# DaisyChainController.net
KiCad netlist of a schematic drawn in EAGLE
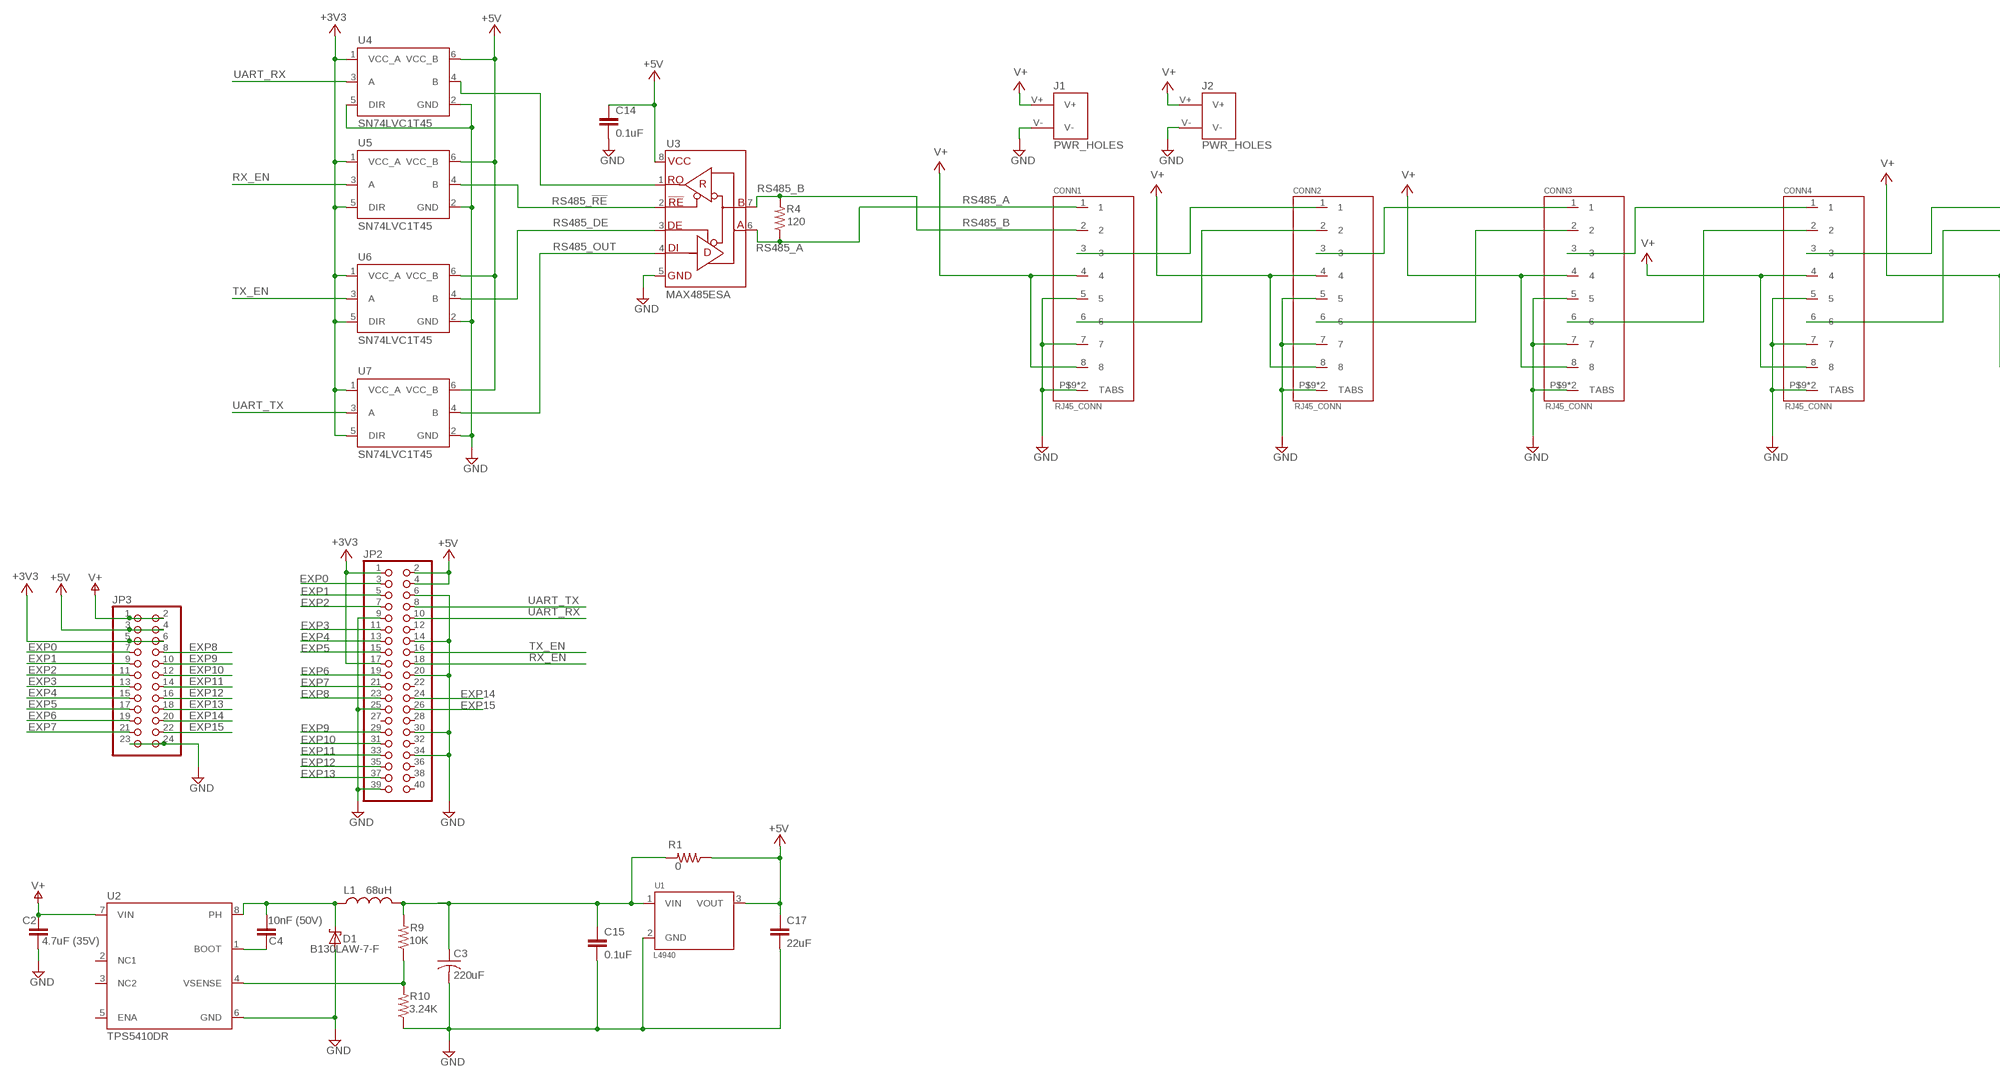
[diagram p0: schematic, sheet 1, part 1 of 2]
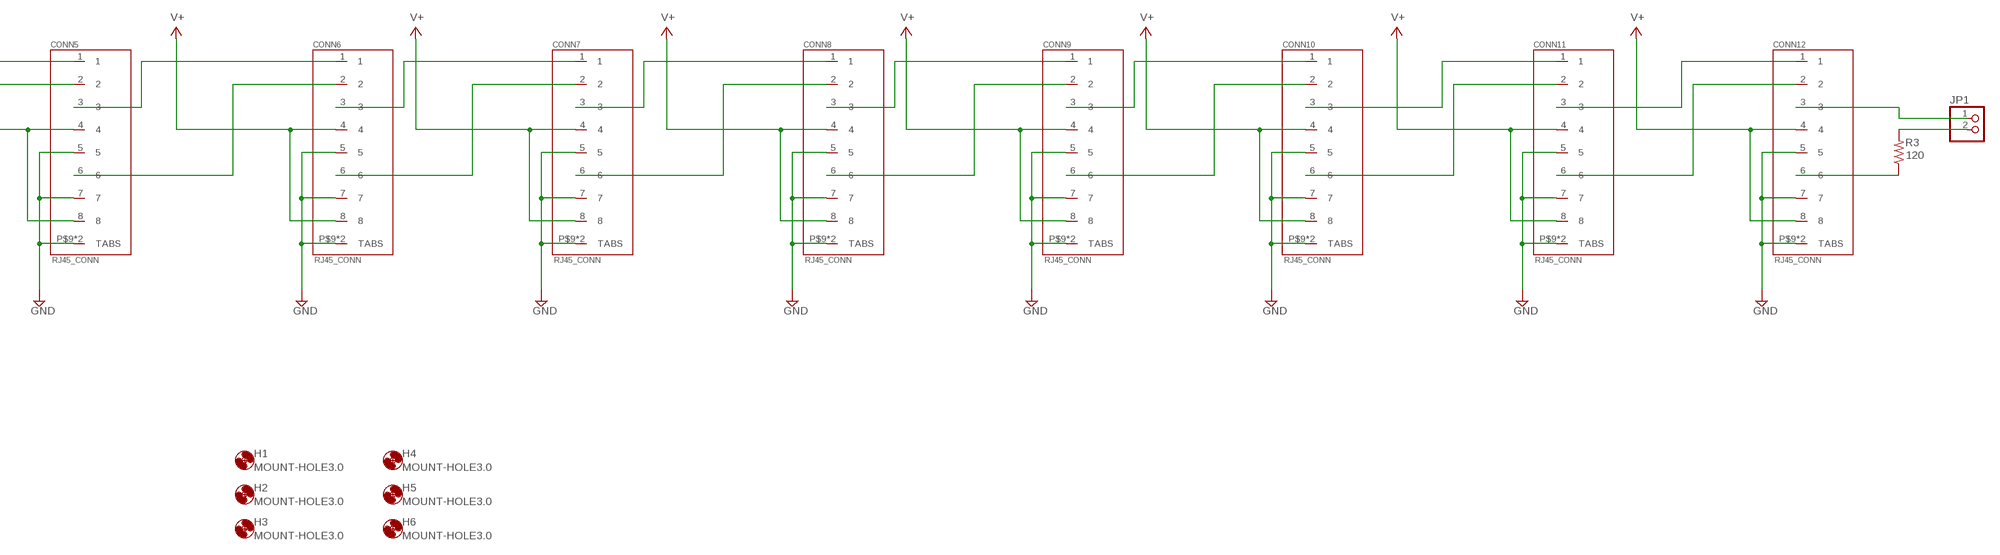
[diagram p1: schematic, sheet 1, part 2 of 2]

(export (version "E")
  (design (tool "Eeschema 10.0.6"))
  (components
    (comp (ref "C2")
      (value "4.7uF (35V)")
      (footprint "eagle-import:C0805")
      (libsource (lib "eagle-import") (part "C-EUC0805"))
    )
    (comp (ref "C3")
      (value "220uF")
      (footprint "eagle-import:KEMET_D_CAP")
      (libsource (lib "eagle-import") (part "TANT_CAP_D"))
    )
    (comp (ref "C4")
      (value "10nF (50V)")
      (footprint "eagle-import:C0805")
      (libsource (lib "eagle-import") (part "C-EUC0805"))
    )
    (comp (ref "C14")
      (value "0.1uF")
      (footprint "eagle-import:C0805")
      (libsource (lib "eagle-import") (part "C-EUC0805"))
    )
    (comp (ref "C15")
      (value "0.1uF")
      (footprint "eagle-import:C0805")
      (libsource (lib "eagle-import") (part "C-EUC0805"))
    )
    (comp (ref "C17")
      (value "22uF")
      (footprint "eagle-import:C0805")
      (libsource (lib "eagle-import") (part "C-EUC0805"))
    )
    (comp (ref "CONN1")
      (value "RJ45_CONN")
      (footprint "eagle-import:RJ45_VERT")
      (libsource (lib "eagle-import") (part "RJ45_CONN"))
    )
    (comp (ref "CONN2")
      (value "RJ45_CONN")
      (footprint "eagle-import:RJ45_VERT")
      (libsource (lib "eagle-import") (part "RJ45_CONN"))
    )
    (comp (ref "CONN3")
      (value "RJ45_CONN")
      (footprint "eagle-import:RJ45_VERT")
      (libsource (lib "eagle-import") (part "RJ45_CONN"))
    )
    (comp (ref "CONN4")
      (value "RJ45_CONN")
      (footprint "eagle-import:RJ45_VERT")
      (libsource (lib "eagle-import") (part "RJ45_CONN"))
    )
    (comp (ref "CONN5")
      (value "RJ45_CONN")
      (footprint "eagle-import:RJ45_VERT")
      (libsource (lib "eagle-import") (part "RJ45_CONN"))
    )
    (comp (ref "CONN6")
      (value "RJ45_CONN")
      (footprint "eagle-import:RJ45_VERT")
      (libsource (lib "eagle-import") (part "RJ45_CONN"))
    )
    (comp (ref "CONN7")
      (value "RJ45_CONN")
      (footprint "eagle-import:RJ45_VERT")
      (libsource (lib "eagle-import") (part "RJ45_CONN"))
    )
    (comp (ref "CONN8")
      (value "RJ45_CONN")
      (footprint "eagle-import:RJ45_VERT")
      (libsource (lib "eagle-import") (part "RJ45_CONN"))
    )
    (comp (ref "CONN9")
      (value "RJ45_CONN")
      (footprint "eagle-import:RJ45_VERT")
      (libsource (lib "eagle-import") (part "RJ45_CONN"))
    )
    (comp (ref "CONN10")
      (value "RJ45_CONN")
      (footprint "eagle-import:RJ45_VERT")
      (libsource (lib "eagle-import") (part "RJ45_CONN"))
    )
    (comp (ref "CONN11")
      (value "RJ45_CONN")
      (footprint "eagle-import:RJ45_VERT")
      (libsource (lib "eagle-import") (part "RJ45_CONN"))
    )
    (comp (ref "CONN12")
      (value "RJ45_CONN")
      (footprint "eagle-import:RJ45_VERT")
      (libsource (lib "eagle-import") (part "RJ45_CONN"))
    )
    (comp (ref "D1")
      (value "B130LAW-7-F")
      (footprint "eagle-import:SOD123")
      (libsource (lib "eagle-import") (part "B130LAW-7-F"))
    )
    (comp (ref "H1")
      (value "MOUNT-HOLE3.0")
      (footprint "eagle-import:3,0")
      (libsource (lib "eagle-import") (part "MOUNT-HOLE3.0"))
    )
    (comp (ref "H2")
      (value "MOUNT-HOLE3.0")
      (footprint "eagle-import:3,0")
      (libsource (lib "eagle-import") (part "MOUNT-HOLE3.0"))
    )
    (comp (ref "H3")
      (value "MOUNT-HOLE3.0")
      (footprint "eagle-import:3,0")
      (libsource (lib "eagle-import") (part "MOUNT-HOLE3.0"))
    )
    (comp (ref "H4")
      (value "MOUNT-HOLE3.0")
      (footprint "eagle-import:3,0")
      (libsource (lib "eagle-import") (part "MOUNT-HOLE3.0"))
    )
    (comp (ref "H5")
      (value "MOUNT-HOLE3.0")
      (footprint "eagle-import:3,0")
      (libsource (lib "eagle-import") (part "MOUNT-HOLE3.0"))
    )
    (comp (ref "H6")
      (value "MOUNT-HOLE3.0")
      (footprint "eagle-import:3,0")
      (libsource (lib "eagle-import") (part "MOUNT-HOLE3.0"))
    )
    (comp (ref "J1")
      (value "PWR_HOLES")
      (footprint "eagle-import:PWR_HOLES")
      (libsource (lib "eagle-import") (part "PWR_HOLES"))
    )
    (comp (ref "J2")
      (value "PWR_HOLES")
      (footprint "eagle-import:PWR_HOLES")
      (libsource (lib "eagle-import") (part "PWR_HOLES"))
    )
    (comp (ref "JP1")
      (value "PINHD-1X2")
      (footprint "eagle-import:1X02")
      (libsource (lib "eagle-import") (part "PINHD-1X2"))
    )
    (comp (ref "JP2")
      (value "PINHD-2X20/90")
      (footprint "eagle-import:2X20_90")
      (libsource (lib "eagle-import") (part "PINHD-2X20/90"))
    )
    (comp (ref "JP3")
      (value "PINHD-2X12")
      (footprint "eagle-import:2X12")
      (libsource (lib "eagle-import") (part "PINHD-2X12"))
    )
    (comp (ref "L1")
      (value "68uH")
      (footprint "eagle-import:CDRH127R")
      (libsource (lib "eagle-import") (part "L_CDRH127"))
    )
    (comp (ref "R1")
      (value "0")
      (footprint "eagle-import:R0805")
      (libsource (lib "eagle-import") (part "R-US_R0805"))
    )
    (comp (ref "R3")
      (value "120")
      (footprint "eagle-import:R0805")
      (libsource (lib "eagle-import") (part "R-US_R0805"))
    )
    (comp (ref "R4")
      (value "120")
      (footprint "eagle-import:R0805")
      (libsource (lib "eagle-import") (part "R-US_R0805"))
    )
    (comp (ref "R9")
      (value "10K")
      (footprint "eagle-import:R0805")
      (libsource (lib "eagle-import") (part "R-US_R0805"))
    )
    (comp (ref "R10")
      (value "3.24K")
      (footprint "eagle-import:R0805")
      (libsource (lib "eagle-import") (part "R-US_R0805"))
    )
    (comp (ref "U1")
      (value "L4940")
      (footprint "eagle-import:TO220")
      (libsource (lib "eagle-import") (part "L4940"))
    )
    (comp (ref "U2")
      (value "TPS5410DR")
      (footprint "eagle-import:SO08")
      (libsource (lib "eagle-import") (part "TPS5410DR"))
    )
    (comp (ref "U3")
      (value "MAX485ESA")
      (footprint "eagle-import:SO08")
      (libsource (lib "eagle-import") (part "MAX485ESA"))
    )
    (comp (ref "U4")
      (value "SN74LVC1T45")
      (footprint "eagle-import:SOT23-6")
      (libsource (lib "eagle-import") (part "SN74LVC1T45"))
    )
    (comp (ref "U5")
      (value "SN74LVC1T45")
      (footprint "eagle-import:SOT23-6")
      (libsource (lib "eagle-import") (part "SN74LVC1T45"))
    )
    (comp (ref "U6")
      (value "SN74LVC1T45")
      (footprint "eagle-import:SOT23-6")
      (libsource (lib "eagle-import") (part "SN74LVC1T45"))
    )
    (comp (ref "U7")
      (value "SN74LVC1T45")
      (footprint "eagle-import:SOT23-6")
      (libsource (lib "eagle-import") (part "SN74LVC1T45"))
    )
  )
  (nets
    (net (code "1") (name "+3V3") (class "Default")
      (node (ref "JP2") (pin "1") (pinfunction "1_1") (pintype "passive"))
      (node (ref "JP2") (pin "17") (pinfunction "17_17") (pintype "passive"))
      (node (ref "JP3") (pin "5") (pinfunction "5_5") (pintype "passive"))
      (node (ref "JP3") (pin "6") (pinfunction "6_6") (pintype "passive"))
      (node (ref "U4") (pin "1") (pinfunction "VCC_A_1") (pintype "power_in"))
      (node (ref "U5") (pin "1") (pinfunction "VCC_A_1") (pintype "power_in"))
      (node (ref "U5") (pin "5") (pinfunction "DIR_5") (pintype "input"))
      (node (ref "U6") (pin "1") (pinfunction "VCC_A_1") (pintype "power_in"))
      (node (ref "U6") (pin "5") (pinfunction "DIR_5") (pintype "input"))
      (node (ref "U7") (pin "1") (pinfunction "VCC_A_1") (pintype "power_in"))
      (node (ref "U7") (pin "5") (pinfunction "DIR_5") (pintype "input"))
    )
    (net (code "2") (name "+5V") (class "Default")
      (node (ref "C14") (pin "1") (pinfunction "1_1") (pintype "passive"))
      (node (ref "C17") (pin "1") (pinfunction "1_1") (pintype "passive"))
      (node (ref "JP2") (pin "2") (pinfunction "2_2") (pintype "passive"))
      (node (ref "JP2") (pin "4") (pinfunction "4_4") (pintype "passive"))
      (node (ref "JP3") (pin "3") (pinfunction "3_3") (pintype "passive"))
      (node (ref "JP3") (pin "4") (pinfunction "4_4") (pintype "passive"))
      (node (ref "R1") (pin "1") (pinfunction "1_1") (pintype "passive"))
      (node (ref "U1") (pin "3") (pinfunction "VOUT_3") (pintype "power_in"))
      (node (ref "U3") (pin "8") (pinfunction "VCC_8") (pintype "power_in"))
      (node (ref "U4") (pin "6") (pinfunction "VCC_B_6") (pintype "power_in"))
      (node (ref "U5") (pin "6") (pinfunction "VCC_B_6") (pintype "power_in"))
      (node (ref "U6") (pin "6") (pinfunction "VCC_B_6") (pintype "power_in"))
      (node (ref "U7") (pin "6") (pinfunction "VCC_B_6") (pintype "power_in"))
    )
    (net (code "3") (name "/EXP0") (class "Default")
      (node (ref "JP2") (pin "3") (pinfunction "3_3") (pintype "passive"))
      (node (ref "JP3") (pin "7") (pinfunction "7_7") (pintype "passive"))
    )
    (net (code "4") (name "/EXP1") (class "Default")
      (node (ref "JP2") (pin "5") (pinfunction "5_5") (pintype "passive"))
      (node (ref "JP3") (pin "9") (pinfunction "9_9") (pintype "passive"))
    )
    (net (code "5") (name "/EXP2") (class "Default")
      (node (ref "JP2") (pin "7") (pinfunction "7_7") (pintype "passive"))
      (node (ref "JP3") (pin "11") (pinfunction "11_11") (pintype "passive"))
    )
    (net (code "6") (name "/EXP3") (class "Default")
      (node (ref "JP2") (pin "11") (pinfunction "11_11") (pintype "passive"))
      (node (ref "JP3") (pin "13") (pinfunction "13_13") (pintype "passive"))
    )
    (net (code "7") (name "/EXP4") (class "Default")
      (node (ref "JP2") (pin "13") (pinfunction "13_13") (pintype "passive"))
      (node (ref "JP3") (pin "15") (pinfunction "15_15") (pintype "passive"))
    )
    (net (code "8") (name "/EXP5") (class "Default")
      (node (ref "JP2") (pin "15") (pinfunction "15_15") (pintype "passive"))
      (node (ref "JP3") (pin "17") (pinfunction "17_17") (pintype "passive"))
    )
    (net (code "9") (name "/EXP6") (class "Default")
      (node (ref "JP2") (pin "19") (pinfunction "19_19") (pintype "passive"))
      (node (ref "JP3") (pin "19") (pinfunction "19_19") (pintype "passive"))
    )
    (net (code "10") (name "/EXP7") (class "Default")
      (node (ref "JP2") (pin "21") (pinfunction "21_21") (pintype "passive"))
      (node (ref "JP3") (pin "21") (pinfunction "21_21") (pintype "passive"))
    )
    (net (code "11") (name "/EXP8") (class "Default")
      (node (ref "JP2") (pin "23") (pinfunction "23_23") (pintype "passive"))
      (node (ref "JP3") (pin "8") (pinfunction "8_8") (pintype "passive"))
    )
    (net (code "12") (name "/EXP9") (class "Default")
      (node (ref "JP2") (pin "29") (pinfunction "29_29") (pintype "passive"))
      (node (ref "JP3") (pin "10") (pinfunction "10_10") (pintype "passive"))
    )
    (net (code "13") (name "/EXP10") (class "Default")
      (node (ref "JP2") (pin "31") (pinfunction "31_31") (pintype "passive"))
      (node (ref "JP3") (pin "12") (pinfunction "12_12") (pintype "passive"))
    )
    (net (code "14") (name "/EXP11") (class "Default")
      (node (ref "JP2") (pin "33") (pinfunction "33_33") (pintype "passive"))
      (node (ref "JP3") (pin "14") (pinfunction "14_14") (pintype "passive"))
    )
    (net (code "15") (name "/EXP12") (class "Default")
      (node (ref "JP2") (pin "35") (pinfunction "35_35") (pintype "passive"))
      (node (ref "JP3") (pin "16") (pinfunction "16_16") (pintype "passive"))
    )
    (net (code "16") (name "/EXP13") (class "Default")
      (node (ref "JP2") (pin "37") (pinfunction "37_37") (pintype "passive"))
      (node (ref "JP3") (pin "18") (pinfunction "18_18") (pintype "passive"))
    )
    (net (code "17") (name "/EXP14") (class "Default")
      (node (ref "JP2") (pin "24") (pinfunction "24_24") (pintype "passive"))
      (node (ref "JP3") (pin "20") (pinfunction "20_20") (pintype "passive"))
    )
    (net (code "18") (name "/EXP15") (class "Default")
      (node (ref "JP2") (pin "26") (pinfunction "26_26") (pintype "passive"))
      (node (ref "JP3") (pin "22") (pinfunction "22_22") (pintype "passive"))
    )
    (net (code "19") (name "/RS485_A") (class "Default")
      (node (ref "CONN1") (pin "1") (pinfunction "1_1") (pintype "bidirectional"))
      (node (ref "R4") (pin "1") (pinfunction "1_1") (pintype "passive"))
      (node (ref "U3") (pin "6") (pinfunction "A_6") (pintype "bidirectional"))
    )
    (net (code "20") (name "/RS485_B") (class "Default")
      (node (ref "CONN1") (pin "2") (pinfunction "2_2") (pintype "bidirectional"))
      (node (ref "R4") (pin "2") (pinfunction "2_2") (pintype "passive"))
      (node (ref "U3") (pin "7") (pinfunction "B_7") (pintype "bidirectional"))
    )
    (net (code "21") (name "/RS485_DE") (class "Default")
      (node (ref "U3") (pin "3") (pinfunction "DE_3") (pintype "input"))
      (node (ref "U6") (pin "4") (pinfunction "B_4") (pintype "bidirectional"))
    )
    (net (code "22") (name "/RS485_OUT") (class "Default")
      (node (ref "U3") (pin "4") (pinfunction "DI_4") (pintype "input"))
      (node (ref "U7") (pin "4") (pinfunction "B_4") (pintype "bidirectional"))
    )
    (net (code "23") (name "/RS485_~{RE}") (class "Default")
      (node (ref "U3") (pin "2") (pinfunction "~{RE}_2") (pintype "output"))
      (node (ref "U5") (pin "4") (pinfunction "B_4") (pintype "bidirectional"))
    )
    (net (code "24") (name "/RX_EN") (class "Default")
      (node (ref "JP2") (pin "18") (pinfunction "18_18") (pintype "passive"))
      (node (ref "U5") (pin "3") (pinfunction "A_3") (pintype "bidirectional"))
    )
    (net (code "25") (name "/TX_EN") (class "Default")
      (node (ref "JP2") (pin "16") (pinfunction "16_16") (pintype "passive"))
      (node (ref "U6") (pin "3") (pinfunction "A_3") (pintype "bidirectional"))
    )
    (net (code "26") (name "/UART_RX") (class "Default")
      (node (ref "JP2") (pin "10") (pinfunction "10_10") (pintype "passive"))
      (node (ref "U4") (pin "3") (pinfunction "A_3") (pintype "bidirectional"))
    )
    (net (code "27") (name "/UART_TX") (class "Default")
      (node (ref "JP2") (pin "8") (pinfunction "8_8") (pintype "passive"))
      (node (ref "U7") (pin "3") (pinfunction "A_3") (pintype "bidirectional"))
    )
    (net (code "28") (name "GND") (class "Default")
      (node (ref "C14") (pin "2") (pinfunction "2_2") (pintype "passive"))
      (node (ref "C15") (pin "2") (pinfunction "2_2") (pintype "passive"))
      (node (ref "C17") (pin "2") (pinfunction "2_2") (pintype "passive"))
      (node (ref "C2") (pin "2") (pinfunction "2_2") (pintype "passive"))
      (node (ref "C3") (pin "-") (pinfunction "2_-") (pintype "passive"))
      (node (ref "CONN1") (pin "5") (pinfunction "5_5") (pintype "bidirectional"))
      (node (ref "CONN1") (pin "7") (pinfunction "7_7") (pintype "bidirectional"))
      (node (ref "CONN1") (pin "P$10") (pinfunction "TABS_P$10") (pintype "bidirectional"))
      (node (ref "CONN1") (pin "P$9") (pinfunction "TABS_P$9") (pintype "bidirectional"))
      (node (ref "CONN10") (pin "5") (pinfunction "5_5") (pintype "bidirectional"))
      (node (ref "CONN10") (pin "7") (pinfunction "7_7") (pintype "bidirectional"))
      (node (ref "CONN10") (pin "P$10") (pinfunction "TABS_P$10") (pintype "bidirectional"))
      (node (ref "CONN10") (pin "P$9") (pinfunction "TABS_P$9") (pintype "bidirectional"))
      (node (ref "CONN11") (pin "5") (pinfunction "5_5") (pintype "bidirectional"))
      (node (ref "CONN11") (pin "7") (pinfunction "7_7") (pintype "bidirectional"))
      (node (ref "CONN11") (pin "P$10") (pinfunction "TABS_P$10") (pintype "bidirectional"))
      (node (ref "CONN11") (pin "P$9") (pinfunction "TABS_P$9") (pintype "bidirectional"))
      (node (ref "CONN12") (pin "5") (pinfunction "5_5") (pintype "bidirectional"))
      (node (ref "CONN12") (pin "7") (pinfunction "7_7") (pintype "bidirectional"))
      (node (ref "CONN12") (pin "P$10") (pinfunction "TABS_P$10") (pintype "bidirectional"))
      (node (ref "CONN12") (pin "P$9") (pinfunction "TABS_P$9") (pintype "bidirectional"))
      (node (ref "CONN2") (pin "5") (pinfunction "5_5") (pintype "bidirectional"))
      (node (ref "CONN2") (pin "7") (pinfunction "7_7") (pintype "bidirectional"))
      (node (ref "CONN2") (pin "P$10") (pinfunction "TABS_P$10") (pintype "bidirectional"))
      (node (ref "CONN2") (pin "P$9") (pinfunction "TABS_P$9") (pintype "bidirectional"))
      (node (ref "CONN3") (pin "5") (pinfunction "5_5") (pintype "bidirectional"))
      (node (ref "CONN3") (pin "7") (pinfunction "7_7") (pintype "bidirectional"))
      (node (ref "CONN3") (pin "P$10") (pinfunction "TABS_P$10") (pintype "bidirectional"))
      (node (ref "CONN3") (pin "P$9") (pinfunction "TABS_P$9") (pintype "bidirectional"))
      (node (ref "CONN4") (pin "5") (pinfunction "5_5") (pintype "bidirectional"))
      (node (ref "CONN4") (pin "7") (pinfunction "7_7") (pintype "bidirectional"))
      (node (ref "CONN4") (pin "P$10") (pinfunction "TABS_P$10") (pintype "bidirectional"))
      (node (ref "CONN4") (pin "P$9") (pinfunction "TABS_P$9") (pintype "bidirectional"))
      (node (ref "CONN5") (pin "5") (pinfunction "5_5") (pintype "bidirectional"))
      (node (ref "CONN5") (pin "7") (pinfunction "7_7") (pintype "bidirectional"))
      (node (ref "CONN5") (pin "P$10") (pinfunction "TABS_P$10") (pintype "bidirectional"))
      (node (ref "CONN5") (pin "P$9") (pinfunction "TABS_P$9") (pintype "bidirectional"))
      (node (ref "CONN6") (pin "5") (pinfunction "5_5") (pintype "bidirectional"))
      (node (ref "CONN6") (pin "7") (pinfunction "7_7") (pintype "bidirectional"))
      (node (ref "CONN6") (pin "P$10") (pinfunction "TABS_P$10") (pintype "bidirectional"))
      (node (ref "CONN6") (pin "P$9") (pinfunction "TABS_P$9") (pintype "bidirectional"))
      (node (ref "CONN7") (pin "5") (pinfunction "5_5") (pintype "bidirectional"))
      (node (ref "CONN7") (pin "7") (pinfunction "7_7") (pintype "bidirectional"))
      (node (ref "CONN7") (pin "P$10") (pinfunction "TABS_P$10") (pintype "bidirectional"))
      (node (ref "CONN7") (pin "P$9") (pinfunction "TABS_P$9") (pintype "bidirectional"))
      (node (ref "CONN8") (pin "5") (pinfunction "5_5") (pintype "bidirectional"))
      (node (ref "CONN8") (pin "7") (pinfunction "7_7") (pintype "bidirectional"))
      (node (ref "CONN8") (pin "P$10") (pinfunction "TABS_P$10") (pintype "bidirectional"))
      (node (ref "CONN8") (pin "P$9") (pinfunction "TABS_P$9") (pintype "bidirectional"))
      (node (ref "CONN9") (pin "5") (pinfunction "5_5") (pintype "bidirectional"))
      (node (ref "CONN9") (pin "7") (pinfunction "7_7") (pintype "bidirectional"))
      (node (ref "CONN9") (pin "P$10") (pinfunction "TABS_P$10") (pintype "bidirectional"))
      (node (ref "CONN9") (pin "P$9") (pinfunction "TABS_P$9") (pintype "bidirectional"))
      (node (ref "D1") (pin "A") (pinfunction "A_A") (pintype "passive"))
      (node (ref "J1") (pin "V-") (pinfunction "V-_V-") (pintype "bidirectional"))
      (node (ref "J2") (pin "V-") (pinfunction "V-_V-") (pintype "bidirectional"))
      (node (ref "JP2") (pin "14") (pinfunction "14_14") (pintype "passive"))
      (node (ref "JP2") (pin "20") (pinfunction "20_20") (pintype "passive"))
      (node (ref "JP2") (pin "25") (pinfunction "25_25") (pintype "passive"))
      (node (ref "JP2") (pin "30") (pinfunction "30_30") (pintype "passive"))
      (node (ref "JP2") (pin "34") (pinfunction "34_34") (pintype "passive"))
      (node (ref "JP2") (pin "39") (pinfunction "39_39") (pintype "passive"))
      (node (ref "JP2") (pin "6") (pinfunction "6_6") (pintype "passive"))
      (node (ref "JP2") (pin "9") (pinfunction "9_9") (pintype "passive"))
      (node (ref "JP3") (pin "23") (pinfunction "23_23") (pintype "passive"))
      (node (ref "JP3") (pin "24") (pinfunction "24_24") (pintype "passive"))
      (node (ref "R10") (pin "1") (pinfunction "1_1") (pintype "passive"))
      (node (ref "U1") (pin "2") (pinfunction "GND_2") (pintype "power_in"))
      (node (ref "U2") (pin "6") (pinfunction "GND_6") (pintype "bidirectional"))
      (node (ref "U3") (pin "5") (pinfunction "GND_5") (pintype "power_in"))
      (node (ref "U4") (pin "2") (pinfunction "GND_2") (pintype "power_in"))
      (node (ref "U4") (pin "5") (pinfunction "DIR_5") (pintype "input"))
      (node (ref "U5") (pin "2") (pinfunction "GND_2") (pintype "power_in"))
      (node (ref "U6") (pin "2") (pinfunction "GND_2") (pintype "power_in"))
      (node (ref "U7") (pin "2") (pinfunction "GND_2") (pintype "power_in"))
    )
    (net (code "29") (name "Net-(C3-1)") (class "Default")
      (node (ref "C15") (pin "1") (pinfunction "1_1") (pintype "passive"))
      (node (ref "C3") (pin "+") (pinfunction "1_+") (pintype "passive"))
      (node (ref "L1") (pin "P$2") (pinfunction "2_P$2") (pintype "passive"))
      (node (ref "R1") (pin "2") (pinfunction "2_2") (pintype "passive"))
      (node (ref "R9") (pin "2") (pinfunction "2_2") (pintype "passive"))
      (node (ref "U1") (pin "1") (pinfunction "VIN_1") (pintype "power_in"))
    )
    (net (code "30") (name "Net-(CONN1-Pad3)") (class "Default")
      (node (ref "CONN1") (pin "3") (pinfunction "3_3") (pintype "bidirectional"))
      (node (ref "CONN2") (pin "1") (pinfunction "1_1") (pintype "bidirectional"))
    )
    (net (code "31") (name "Net-(CONN1-Pad6)") (class "Default")
      (node (ref "CONN1") (pin "6") (pinfunction "6_6") (pintype "bidirectional"))
      (node (ref "CONN2") (pin "2") (pinfunction "2_2") (pintype "bidirectional"))
    )
    (net (code "32") (name "Net-(CONN2-Pad3)") (class "Default")
      (node (ref "CONN2") (pin "3") (pinfunction "3_3") (pintype "bidirectional"))
      (node (ref "CONN3") (pin "1") (pinfunction "1_1") (pintype "bidirectional"))
    )
    (net (code "33") (name "Net-(CONN2-Pad6)") (class "Default")
      (node (ref "CONN2") (pin "6") (pinfunction "6_6") (pintype "bidirectional"))
      (node (ref "CONN3") (pin "2") (pinfunction "2_2") (pintype "bidirectional"))
    )
    (net (code "34") (name "Net-(CONN3-Pad3)") (class "Default")
      (node (ref "CONN3") (pin "3") (pinfunction "3_3") (pintype "bidirectional"))
      (node (ref "CONN4") (pin "1") (pinfunction "1_1") (pintype "bidirectional"))
    )
    (net (code "35") (name "Net-(CONN3-Pad6)") (class "Default")
      (node (ref "CONN3") (pin "6") (pinfunction "6_6") (pintype "bidirectional"))
      (node (ref "CONN4") (pin "2") (pinfunction "2_2") (pintype "bidirectional"))
    )
    (net (code "36") (name "Net-(CONN4-Pad3)") (class "Default")
      (node (ref "CONN4") (pin "3") (pinfunction "3_3") (pintype "bidirectional"))
      (node (ref "CONN5") (pin "1") (pinfunction "1_1") (pintype "bidirectional"))
    )
    (net (code "37") (name "Net-(CONN4-Pad6)") (class "Default")
      (node (ref "CONN4") (pin "6") (pinfunction "6_6") (pintype "bidirectional"))
      (node (ref "CONN5") (pin "2") (pinfunction "2_2") (pintype "bidirectional"))
    )
    (net (code "38") (name "Net-(CONN5-Pad3)") (class "Default")
      (node (ref "CONN5") (pin "3") (pinfunction "3_3") (pintype "bidirectional"))
      (node (ref "CONN6") (pin "1") (pinfunction "1_1") (pintype "bidirectional"))
    )
    (net (code "39") (name "Net-(CONN5-Pad6)") (class "Default")
      (node (ref "CONN5") (pin "6") (pinfunction "6_6") (pintype "bidirectional"))
      (node (ref "CONN6") (pin "2") (pinfunction "2_2") (pintype "bidirectional"))
    )
    (net (code "40") (name "Net-(CONN6-Pad3)") (class "Default")
      (node (ref "CONN6") (pin "3") (pinfunction "3_3") (pintype "bidirectional"))
      (node (ref "CONN7") (pin "1") (pinfunction "1_1") (pintype "bidirectional"))
    )
    (net (code "41") (name "Net-(CONN6-Pad6)") (class "Default")
      (node (ref "CONN6") (pin "6") (pinfunction "6_6") (pintype "bidirectional"))
      (node (ref "CONN7") (pin "2") (pinfunction "2_2") (pintype "bidirectional"))
    )
    (net (code "42") (name "Net-(CONN7-Pad3)") (class "Default")
      (node (ref "CONN7") (pin "3") (pinfunction "3_3") (pintype "bidirectional"))
      (node (ref "CONN8") (pin "1") (pinfunction "1_1") (pintype "bidirectional"))
    )
    (net (code "43") (name "Net-(CONN7-Pad6)") (class "Default")
      (node (ref "CONN7") (pin "6") (pinfunction "6_6") (pintype "bidirectional"))
      (node (ref "CONN8") (pin "2") (pinfunction "2_2") (pintype "bidirectional"))
    )
    (net (code "44") (name "Net-(CONN8-Pad3)") (class "Default")
      (node (ref "CONN8") (pin "3") (pinfunction "3_3") (pintype "bidirectional"))
      (node (ref "CONN9") (pin "1") (pinfunction "1_1") (pintype "bidirectional"))
    )
    (net (code "45") (name "Net-(CONN8-Pad6)") (class "Default")
      (node (ref "CONN8") (pin "6") (pinfunction "6_6") (pintype "bidirectional"))
      (node (ref "CONN9") (pin "2") (pinfunction "2_2") (pintype "bidirectional"))
    )
    (net (code "46") (name "Net-(CONN10-Pad1)") (class "Default")
      (node (ref "CONN10") (pin "1") (pinfunction "1_1") (pintype "bidirectional"))
      (node (ref "CONN9") (pin "3") (pinfunction "3_3") (pintype "bidirectional"))
    )
    (net (code "47") (name "Net-(CONN10-Pad2)") (class "Default")
      (node (ref "CONN10") (pin "2") (pinfunction "2_2") (pintype "bidirectional"))
      (node (ref "CONN9") (pin "6") (pinfunction "6_6") (pintype "bidirectional"))
    )
    (net (code "48") (name "Net-(CONN10-Pad3)") (class "Default")
      (node (ref "CONN10") (pin "3") (pinfunction "3_3") (pintype "bidirectional"))
      (node (ref "CONN11") (pin "1") (pinfunction "1_1") (pintype "bidirectional"))
    )
    (net (code "49") (name "Net-(CONN10-Pad6)") (class "Default")
      (node (ref "CONN10") (pin "6") (pinfunction "6_6") (pintype "bidirectional"))
      (node (ref "CONN11") (pin "2") (pinfunction "2_2") (pintype "bidirectional"))
    )
    (net (code "50") (name "Net-(CONN11-Pad3)") (class "Default")
      (node (ref "CONN11") (pin "3") (pinfunction "3_3") (pintype "bidirectional"))
      (node (ref "CONN12") (pin "1") (pinfunction "1_1") (pintype "bidirectional"))
    )
    (net (code "51") (name "Net-(CONN11-Pad6)") (class "Default")
      (node (ref "CONN11") (pin "6") (pinfunction "6_6") (pintype "bidirectional"))
      (node (ref "CONN12") (pin "2") (pinfunction "2_2") (pintype "bidirectional"))
    )
    (net (code "52") (name "Net-(CONN12-Pad3)") (class "Default")
      (node (ref "CONN12") (pin "3") (pinfunction "3_3") (pintype "bidirectional"))
      (node (ref "JP1") (pin "1") (pinfunction "1_1") (pintype "passive"))
    )
    (net (code "53") (name "Net-(CONN12-Pad6)") (class "Default")
      (node (ref "CONN12") (pin "6") (pinfunction "6_6") (pintype "bidirectional"))
      (node (ref "R3") (pin "1") (pinfunction "1_1") (pintype "passive"))
    )
    (net (code "54") (name "Net-(JP1-Pad2)") (class "Default")
      (node (ref "JP1") (pin "2") (pinfunction "2_2") (pintype "passive"))
      (node (ref "R3") (pin "2") (pinfunction "2_2") (pintype "passive"))
    )
    (net (code "55") (name "Net-(U2-BOOT)") (class "Default")
      (node (ref "C4") (pin "2") (pinfunction "2_2") (pintype "passive"))
      (node (ref "U2") (pin "1") (pinfunction "BOOT_1") (pintype "bidirectional"))
    )
    (net (code "56") (name "Net-(U2-PH)") (class "Default")
      (node (ref "C4") (pin "1") (pinfunction "1_1") (pintype "passive"))
      (node (ref "D1") (pin "C") (pinfunction "C_C") (pintype "passive"))
      (node (ref "L1") (pin "1") (pinfunction "1_1") (pintype "passive"))
      (node (ref "U2") (pin "8") (pinfunction "PH_8") (pintype "bidirectional"))
    )
    (net (code "57") (name "Net-(U2-VSENSE)") (class "Default")
      (node (ref "R10") (pin "2") (pinfunction "2_2") (pintype "passive"))
      (node (ref "R9") (pin "1") (pinfunction "1_1") (pintype "passive"))
      (node (ref "U2") (pin "4") (pinfunction "VSENSE_4") (pintype "bidirectional"))
    )
    (net (code "58") (name "Net-(U3-RO)") (class "Default")
      (node (ref "U3") (pin "1") (pinfunction "RO_1") (pintype "output"))
      (node (ref "U4") (pin "4") (pinfunction "B_4") (pintype "bidirectional"))
    )
    (net (code "59") (name "V+") (class "Default")
      (node (ref "C2") (pin "1") (pinfunction "1_1") (pintype "passive"))
      (node (ref "CONN1") (pin "4") (pinfunction "4_4") (pintype "bidirectional"))
      (node (ref "CONN1") (pin "8") (pinfunction "8_8") (pintype "bidirectional"))
      (node (ref "CONN10") (pin "4") (pinfunction "4_4") (pintype "bidirectional"))
      (node (ref "CONN10") (pin "8") (pinfunction "8_8") (pintype "bidirectional"))
      (node (ref "CONN11") (pin "4") (pinfunction "4_4") (pintype "bidirectional"))
      (node (ref "CONN11") (pin "8") (pinfunction "8_8") (pintype "bidirectional"))
      (node (ref "CONN12") (pin "4") (pinfunction "4_4") (pintype "bidirectional"))
      (node (ref "CONN12") (pin "8") (pinfunction "8_8") (pintype "bidirectional"))
      (node (ref "CONN2") (pin "4") (pinfunction "4_4") (pintype "bidirectional"))
      (node (ref "CONN2") (pin "8") (pinfunction "8_8") (pintype "bidirectional"))
      (node (ref "CONN3") (pin "4") (pinfunction "4_4") (pintype "bidirectional"))
      (node (ref "CONN3") (pin "8") (pinfunction "8_8") (pintype "bidirectional"))
      (node (ref "CONN4") (pin "4") (pinfunction "4_4") (pintype "bidirectional"))
      (node (ref "CONN4") (pin "8") (pinfunction "8_8") (pintype "bidirectional"))
      (node (ref "CONN5") (pin "4") (pinfunction "4_4") (pintype "bidirectional"))
      (node (ref "CONN5") (pin "8") (pinfunction "8_8") (pintype "bidirectional"))
      (node (ref "CONN6") (pin "4") (pinfunction "4_4") (pintype "bidirectional"))
      (node (ref "CONN6") (pin "8") (pinfunction "8_8") (pintype "bidirectional"))
      (node (ref "CONN7") (pin "4") (pinfunction "4_4") (pintype "bidirectional"))
      (node (ref "CONN7") (pin "8") (pinfunction "8_8") (pintype "bidirectional"))
      (node (ref "CONN8") (pin "4") (pinfunction "4_4") (pintype "bidirectional"))
      (node (ref "CONN8") (pin "8") (pinfunction "8_8") (pintype "bidirectional"))
      (node (ref "CONN9") (pin "4") (pinfunction "4_4") (pintype "bidirectional"))
      (node (ref "CONN9") (pin "8") (pinfunction "8_8") (pintype "bidirectional"))
      (node (ref "J1") (pin "V+") (pinfunction "V+_V+") (pintype "bidirectional"))
      (node (ref "J2") (pin "V+") (pinfunction "V+_V+") (pintype "bidirectional"))
      (node (ref "JP3") (pin "1") (pinfunction "1_1") (pintype "passive"))
      (node (ref "JP3") (pin "2") (pinfunction "2_2") (pintype "passive"))
      (node (ref "U2") (pin "7") (pinfunction "VIN_7") (pintype "bidirectional"))
    )
    (net (code "60") (name "unconnected-(JP2-Pad12)") (class "Default")
      (node (ref "JP2") (pin "12") (pinfunction "12_12") (pintype "passive"))
    )
    (net (code "61") (name "unconnected-(JP2-Pad22)") (class "Default")
      (node (ref "JP2") (pin "22") (pinfunction "22_22") (pintype "passive"))
    )
    (net (code "62") (name "unconnected-(JP2-Pad27)") (class "Default")
      (node (ref "JP2") (pin "27") (pinfunction "27_27") (pintype "passive"))
    )
    (net (code "63") (name "unconnected-(JP2-Pad28)") (class "Default")
      (node (ref "JP2") (pin "28") (pinfunction "28_28") (pintype "passive"))
    )
    (net (code "64") (name "unconnected-(JP2-Pad32)") (class "Default")
      (node (ref "JP2") (pin "32") (pinfunction "32_32") (pintype "passive"))
    )
    (net (code "65") (name "unconnected-(JP2-Pad36)") (class "Default")
      (node (ref "JP2") (pin "36") (pinfunction "36_36") (pintype "passive"))
    )
    (net (code "66") (name "unconnected-(JP2-Pad38)") (class "Default")
      (node (ref "JP2") (pin "38") (pinfunction "38_38") (pintype "passive"))
    )
    (net (code "67") (name "unconnected-(JP2-Pad40)") (class "Default")
      (node (ref "JP2") (pin "40") (pinfunction "40_40") (pintype "passive"))
    )
    (net (code "68") (name "unconnected-(U2-ENA-Pad5)") (class "Default")
      (node (ref "U2") (pin "5") (pinfunction "ENA_5") (pintype "bidirectional"))
    )
    (net (code "69") (name "unconnected-(U2-NC1-Pad2)") (class "Default")
      (node (ref "U2") (pin "2") (pinfunction "NC1_2") (pintype "bidirectional"))
    )
    (net (code "70") (name "unconnected-(U2-NC2-Pad3)") (class "Default")
      (node (ref "U2") (pin "3") (pinfunction "NC2_3") (pintype "bidirectional"))
    )
  )
)
